# Power_section.net
KiCad netlist of a schematic drawn in Altium Designer
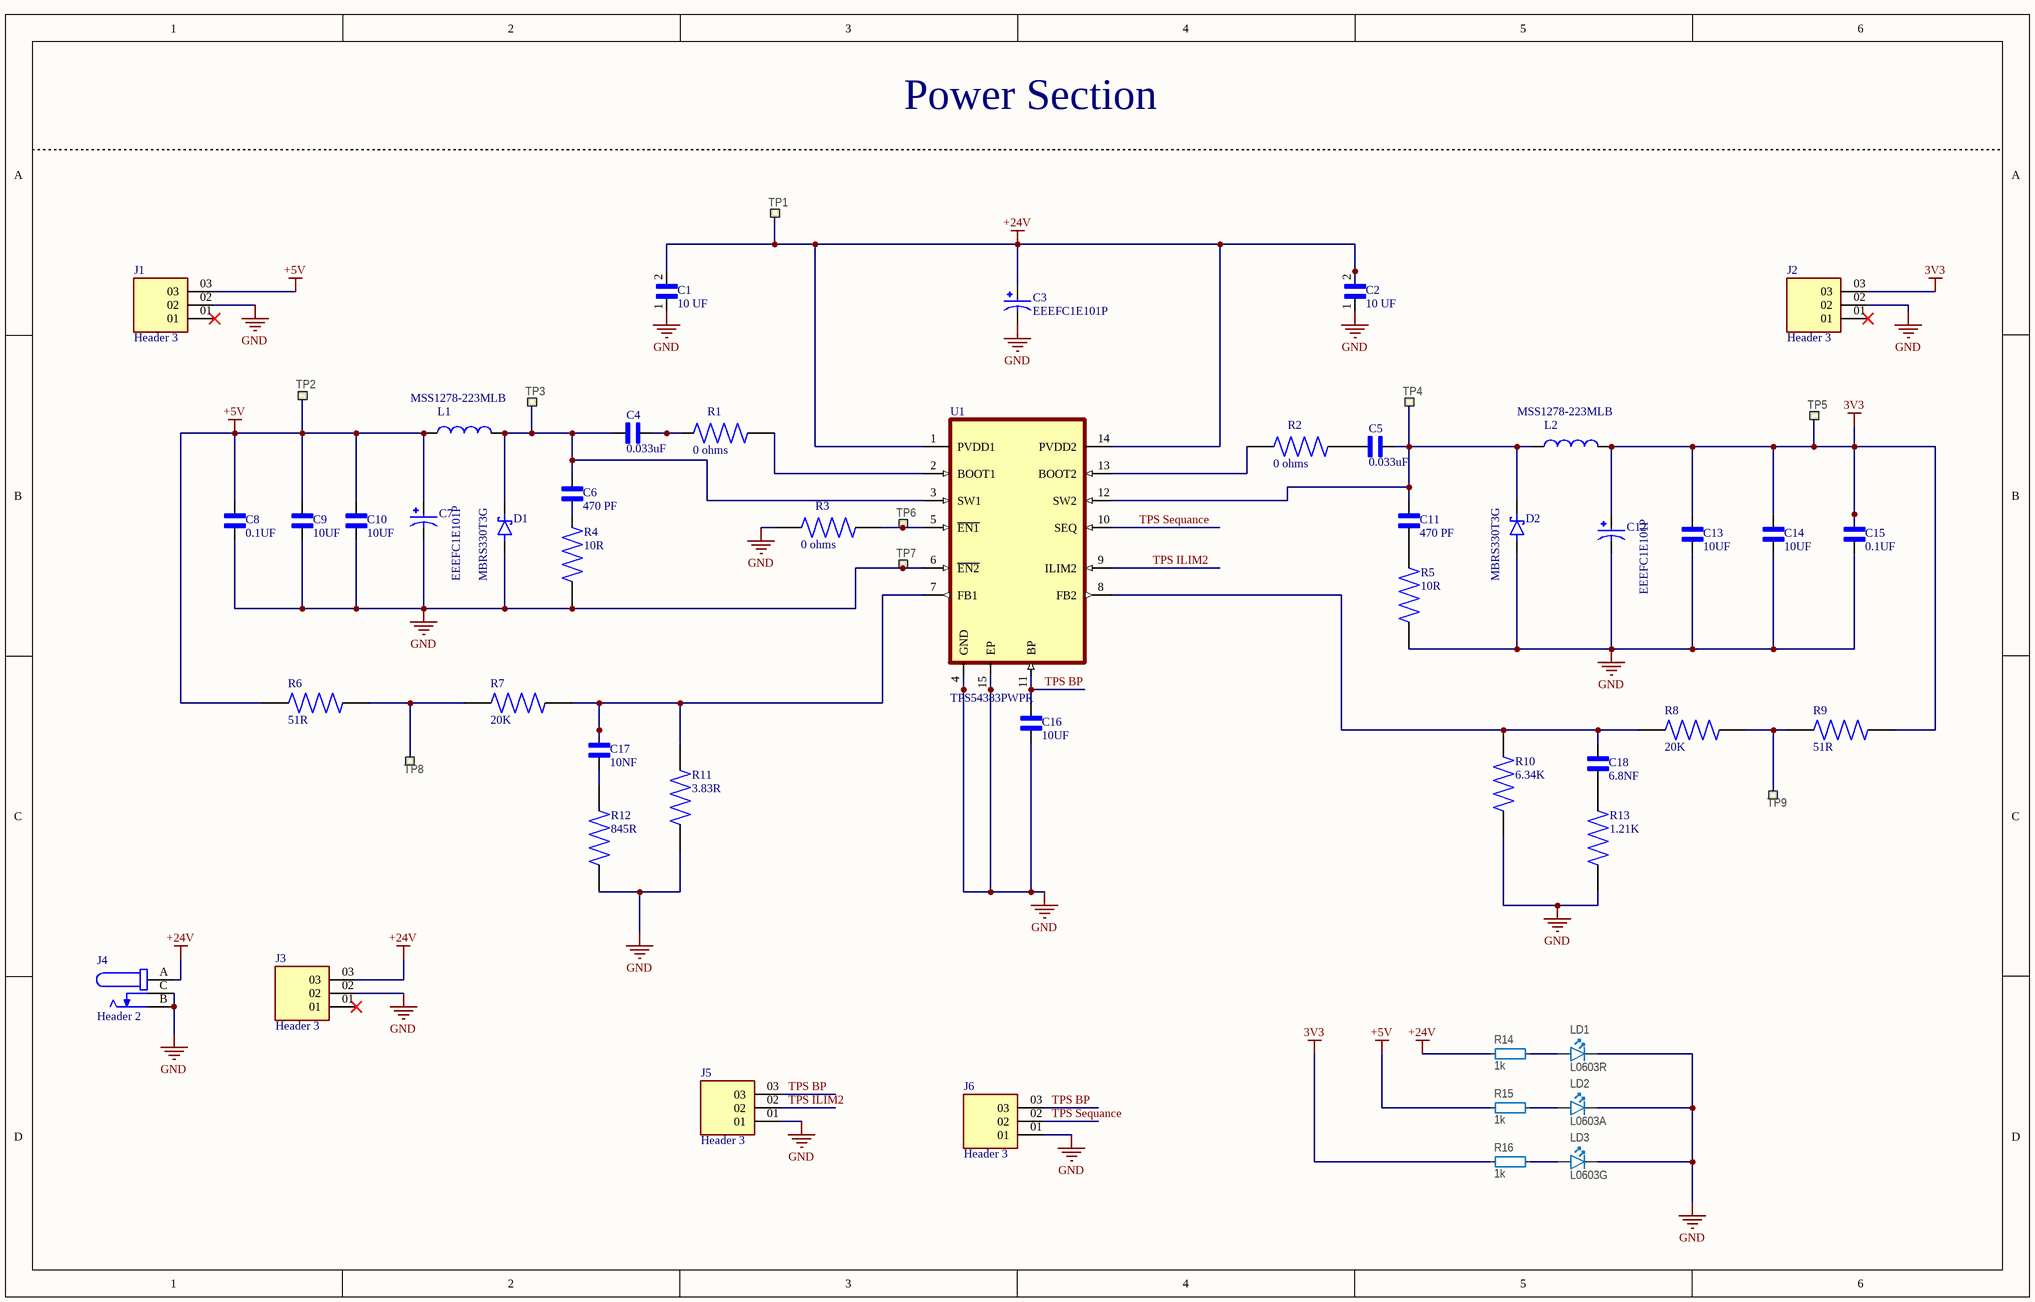
[diagram p0: Power section.SchDoc]

(export (version "E")
  (design (tool "Eeschema 10.0.6"))
  (components
    (comp (ref "C1")
      (value "10 UF")
      (footprint "CAPC3216X180N")
      (description "10礔 卤20% 25V Ceramic Capacitor 1206 (3216 Metric)")
      (fields (field (name "MF") "TDK") (field (name "DIGI-KEY_PART_NUMBER") "445-7708-2-ND"))
      (libsource (lib "C3216X5R1E106M160AB") (part "C3216X5R1E106M160AB"))
    )
    (comp (ref "C2")
      (value "10 UF")
      (footprint "CAPC3216X180N")
      (description "10礔 卤20% 25V Ceramic Capacitor 1206 (3216 Metric)")
      (fields (field (name "MF") "TDK") (field (name "DIGI-KEY_PART_NUMBER") "445-7708-2-ND"))
      (libsource (lib "C3216X5R1E106M160AB") (part "C3216X5R1E106M160AB"))
    )
    (comp (ref "C3")
      (value "EEEFC1E101P")
      (footprint "CAP_EEEFC1E101P")
      (fields (field (name "MF") "Panasonic") (field (name "MP") "EEE-FC1E101P"))
      (libsource (lib "EEEFC1E101P") (part "EEEFC1E101P"))
    )
    (comp (ref "C4")
      (value "0.033uF")
      (footprint "CAPC1608X90")
      (description "Capacitor, ceramic, 25 V, X7R, 20%, .033 μF, 0603")
      (fields (field (name "MF") "KEMET") (field (name "MP") "C0603C104J3RACTU"))
      (libsource (lib "") (part "C0603C104J3RACTU_1"))
    )
    (comp (ref "C5")
      (value "0.033uF")
      (footprint "CAPC1608X90")
      (description "Capacitor, ceramic, 25 V, X7R, 20%, .033 μF, 0603")
      (fields (field (name "MF") "KEMET") (field (name "MP") "C0603C104J3RACTU"))
      (libsource (lib "") (part "C0603C104J3RACTU_1"))
    )
    (comp (ref "C6")
      (value "470 PF")
      (footprint "CAPC1608X90")
      (description "Capacitor, ceramic, 25 V, X7R, 20%, 470 pF, 0603")
      (fields (field (name "MF") "KEMET") (field (name "MP") "C0603C104J3RACTU"))
      (libsource (lib "Accelo Integrated_Library") (part "C0603C104J3RACTU"))
    )
    (comp (ref "C7")
      (value "EEEFC1E101P")
      (footprint "CAP_EEEFC1E101P")
      (fields (field (name "MF") "Panasonic") (field (name "MP") "EEE-FC1E101P"))
      (libsource (lib "EEEFC1E101P") (part "EEEFC1E101P"))
    )
    (comp (ref "C8")
      (value "0.1UF")
      (footprint "CAPC1608X90")
      (description "Capacitor, ceramic, 10 V, X7R, 20%, 0.1 μF, 0603")
      (fields (field (name "MF") "KEMET") (field (name "MP") "C0603C104J3RACTU"))
      (libsource (lib "Accelo Integrated_Library") (part "C0603C104J3RACTU"))
    )
    (comp (ref "C9")
      (value "10UF")
      (footprint "CAPC2012X140N")
      (description "Capacitor, ceramic, 6.3 V, X5R, 20%, 10 μF, 0805")
      (fields (field (name "MF") "AVX") (field (name "MP") "0805ZD474MAT2A"))
      (libsource (lib "0805ZD474MAT2A") (part "0805ZD474MAT2A"))
    )
    (comp (ref "C10")
      (value "10UF")
      (footprint "CAPC2012X140N")
      (description "Capacitor, ceramic, 6.3 V, X5R, 20%, 10 μF, 0805")
      (fields (field (name "MF") "AVX") (field (name "MP") "0805ZD474MAT2A"))
      (libsource (lib "0805ZD474MAT2A") (part "0805ZD474MAT2A"))
    )
    (comp (ref "C11")
      (value "470 PF")
      (footprint "CAPC1608X90")
      (description "Capacitor, ceramic, 25 V, X7R, 20%, 470 pF, 0603")
      (fields (field (name "MF") "KEMET") (field (name "MP") "C0603C104J3RACTU"))
      (libsource (lib "Accelo Integrated_Library") (part "C0603C104J3RACTU"))
    )
    (comp (ref "C12")
      (value "EEEFC1E101P")
      (footprint "CAP_EEEFC1E101P")
      (fields (field (name "MF") "Panasonic") (field (name "MP") "EEE-FC1E101P"))
      (libsource (lib "EEEFC1E101P") (part "EEEFC1E101P"))
    )
    (comp (ref "C13")
      (value "10UF")
      (footprint "CAPC2012X140N")
      (description "Capacitor, ceramic, 6.3 V, X5R, 20%, 10 μF, 0805")
      (fields (field (name "MF") "AVX") (field (name "MP") "0805ZD474MAT2A"))
      (libsource (lib "0805ZD474MAT2A") (part "0805ZD474MAT2A"))
    )
    (comp (ref "C14")
      (value "10UF")
      (footprint "CAPC2012X140N")
      (description "Capacitor, ceramic, 6.3 V, X5R, 20%, 10 μF, 0805")
      (fields (field (name "MF") "AVX") (field (name "MP") "0805ZD474MAT2A"))
      (libsource (lib "0805ZD474MAT2A") (part "0805ZD474MAT2A"))
    )
    (comp (ref "C15")
      (value "0.1UF")
      (footprint "CAPC1608X90")
      (description "Capacitor, ceramic, 10 V, X7R, 20%, 0.1 μF, 0603")
      (fields (field (name "MF") "KEMET") (field (name "MP") "C0603C104J3RACTU"))
      (libsource (lib "Accelo Integrated_Library") (part "C0603C104J3RACTU"))
    )
    (comp (ref "C16")
      (value "10UF")
      (footprint "CAPC2012X140N")
      (description "0.47 ÂµF Â±20% 10V Ceramic Capacitor X5R 0805 (2012 Metric)")
      (fields (field (name "MF") "AVX") (field (name "MP") "0805ZD474MAT2A"))
      (libsource (lib "0805ZD474MAT2A") (part "0805ZD474MAT2A"))
    )
    (comp (ref "C17")
      (value "10NF")
      (footprint "CAPC1608X90")
      (fields (field (name "MF") "KEMET") (field (name "MP") "C0603C104J3RACTU"))
      (libsource (lib "Accelo Integrated_Library") (part "C0603C104J3RACTU"))
    )
    (comp (ref "C18")
      (value "6.8NF")
      (footprint "CAPC1608X90")
      (fields (field (name "MF") "KEMET") (field (name "MP") "C0603C104J3RACTU"))
      (libsource (lib "Accelo Integrated_Library") (part "C0603C104J3RACTU"))
    )
    (comp (ref "D1")
      (value "MBRS330T3G")
      (footprint "DIOM7959X261N")
      (description "Diode Schottky 30 V 3A Surface Mount SMC")
      (fields (field (name "MF") "ON Semiconductor"))
      (libsource (lib "MBRS330T3G") (part "MBRS330T3G"))
    )
    (comp (ref "D2")
      (value "MBRS330T3G")
      (footprint "DIOM7959X261N")
      (description "Diode Schottky 30 V 3A Surface Mount SMC")
      (fields (field (name "MF") "ON Semiconductor"))
      (libsource (lib "MBRS330T3G") (part "MBRS330T3G"))
    )
    (comp (ref "J1")
      (value "Header 3")
      (footprint "SAMTEC_HMTSW-103-XX-X-S-XXX")
      (description "Connector Unshrouded Header 3 Position 2.54mm Solder Straight Through Hole")
      (fields (field (name "MF") "Samtec") (field (name "MP") "HMTSW-103-10-T-S-330"))
      (libsource (lib "Accelo Integrated_Library") (part "HMTSW-103-XX-X-S-XXX"))
    )
    (comp (ref "J2")
      (value "Header 3")
      (footprint "SAMTEC_HMTSW-103-XX-X-S-XXX")
      (description "Connector Unshrouded Header 3 Position 2.54mm Solder Straight Through Hole")
      (fields (field (name "MF") "Samtec") (field (name "MP") "HMTSW-103-10-T-S-330"))
      (libsource (lib "Accelo Integrated_Library") (part "HMTSW-103-XX-X-S-XXX"))
    )
    (comp (ref "J3")
      (value "Header 3")
      (footprint "SAMTEC_HMTSW-103-XX-X-S-XXX")
      (description "Connector Unshrouded Header 3 Position 2.54mm Solder Straight Through Hole")
      (fields (field (name "MF") "Samtec") (field (name "MP") "HMTSW-103-10-T-S-330"))
      (libsource (lib "Accelo Integrated_Library") (part "HMTSW-103-XX-X-S-XXX"))
    )
    (comp (ref "J4")
      (value "Header 2")
      (footprint "TENSILITY_54-00129")
      (description "Connector, dc jack 5.5x2.1 mm, PCB mount, 90 degrees, silver plated, thru hole")
      (fields (field (name "MF") "Tensility International Corp") (field (name "MP") "54-00129"))
      (libsource (lib "54-00129") (part "54-00129"))
    )
    (comp (ref "J5")
      (value "Header 3")
      (footprint "SAMTEC_HMTSW-103-XX-X-S-XXX")
      (description "Connector Unshrouded Header 3 Position 2.54mm Solder Straight Through Hole")
      (fields (field (name "MF") "Samtec") (field (name "MP") "HMTSW-103-10-T-S-330"))
      (libsource (lib "Accelo Integrated_Library") (part "HMTSW-103-XX-X-S-XXX"))
    )
    (comp (ref "J6")
      (value "Header 3")
      (footprint "SAMTEC_HMTSW-103-XX-X-S-XXX")
      (description "Connector Unshrouded Header 3 Position 2.54mm Solder Straight Through Hole")
      (fields (field (name "MF") "Samtec") (field (name "MP") "HMTSW-103-10-T-S-330"))
      (libsource (lib "Accelo Integrated_Library") (part "HMTSW-103-XX-X-S-XXX"))
    )
    (comp (ref "L1")
      (value "MSS1278-223MLB")
      (footprint "IND_MSS1278-223MLB")
      (description "Fixed Inductors 22uH Shld 20% 4A 39.5mOhms AECQ2")
      (fields (field (name "MF") "Coilcraft"))
      (libsource (lib "MSS1278-223MLB") (part "MSS1278-223MLB"))
    )
    (comp (ref "L2")
      (value "MSS1278-223MLB")
      (footprint "IND_MSS1278-223MLB")
      (description "Fixed Inductors 22uH Shld 20% 4A 39.5mOhms AECQ2")
      (fields (field (name "MF") "Coilcraft"))
      (libsource (lib "MSS1278-223MLB") (part "MSS1278-223MLB"))
    )
    (comp (ref "LD1")
      (value "L0603R")
      (footprint "LED_0603_R")
      (description "LED, Red, 0603, Vf=2V, - 40 to +100°C")
      (fields
        (field (name "PART NUMBER") "ASMT-RR45-AQ902")
        (field (name "MANUFACTURER") "Avago")
        (field (name "AUTHOR") "rsk")
      )
      (libsource (lib "pca10152") (part "ASMT-RR45-AQ902"))
    )
    (comp (ref "LD2")
      (value "L0603A")
      (footprint "LED_0603_Y")
      (description "LED, Amber, 0603,  Vf=2V, - 40 to +100°C")
      (fields
        (field (name "PART NUMBER") "ASMT-RA45-AP932")
        (field (name "MANUFACTURER") "Avago")
        (field (name "AUTHOR") "rsk")
      )
      (libsource (lib "pca10152") (part "ASMT-RA45-AP932"))
    )
    (comp (ref "LD3")
      (value "L0603G")
      (footprint "LED_0603_G")
      (description "LED, Yellow Green, 0603, Vf=2V, - 40 to +100°C")
      (fields
        (field (name "PART NUMBER") "ASMT-RF45-AN002")
        (field (name "MANUFACTURER") "Avago")
        (field (name "AUTHOR") "rsk")
      )
      (libsource (lib "pca10152") (part "ASMT-RF45-AN002"))
    )
    (comp (ref "R1")
      (value "0 ohms")
      (footprint "RESC1608X55N")
      (description "Resistor, chip, 1/16 W, 5%, 0 Ω, 0603")
      (fields (field (name "MF") "Yageo") (field (name "MP") "RC0603JR-0751RL"))
      (libsource (lib "RC0603JR-0751RL") (part "RC0603JR-0751RL"))
    )
    (comp (ref "R2")
      (value "0 ohms")
      (footprint "RESC1608X55N")
      (description "Resistor, chip, 1/16 W, 5%, 0 Ω, 0603")
      (fields (field (name "MF") "Yageo") (field (name "MP") "RC0603JR-0751RL"))
      (libsource (lib "RC0603JR-0751RL") (part "RC0603JR-0751RL"))
    )
    (comp (ref "R3")
      (value "0 ohms")
      (footprint "RESC1608X55N")
      (description "Resistor, chip, 1/16 W, 5%, 0 Ω, 0603")
      (fields (field (name "MF") "Yageo") (field (name "MP") "RC0603JR-0751RL"))
      (libsource (lib "RC0603JR-0751RL") (part "RC0603JR-0751RL"))
    )
    (comp (ref "R4")
      (value "10R")
      (footprint "RESC1608X55N")
      (description "Resistor, chip, 1/16 W, 5%, 10 Ω, 0603")
      (fields (field (name "MF") "Yageo") (field (name "MP") "RC0603JR-0751RL"))
      (libsource (lib "RC0603JR-0751RL") (part "RC0603JR-0751RL"))
    )
    (comp (ref "R5")
      (value "10R")
      (footprint "RESC1608X55N")
      (description "Resistor, chip, 1/16 W, 5%, 10 Ω, 0603")
      (fields (field (name "MF") "Yageo") (field (name "MP") "RC0603JR-0751RL"))
      (libsource (lib "RC0603JR-0751RL") (part "RC0603JR-0751RL"))
    )
    (comp (ref "R6")
      (value "51R")
      (footprint "RESC1608X55N")
      (description "51 Ohms Â±5% 0.1W, 1/10W Chip Resistor 0603 (1608 Metric) Moisture Resistant Thick Film")
      (fields (field (name "MF") "Yageo") (field (name "MP") "RC0603JR-0751RL"))
      (libsource (lib "RC0603JR-0751RL") (part "RC0603JR-0751RL"))
    )
    (comp (ref "R7")
      (value "20K")
      (footprint "RESC1608X55N")
      (description "51 Ohms Â±5% 0.1W, 1/10W Chip Resistor 0603 (1608 Metric) Moisture Resistant Thick Film")
      (fields (field (name "MF") "Yageo") (field (name "MP") "RC0603JR-0751RL"))
      (libsource (lib "RC0603JR-0751RL") (part "RC0603JR-0751RL"))
    )
    (comp (ref "R8")
      (value "20K")
      (footprint "RESC1608X55N")
      (description "51 Ohms Â±5% 0.1W, 1/10W Chip Resistor 0603 (1608 Metric) Moisture Resistant Thick Film")
      (fields (field (name "MF") "Yageo") (field (name "MP") "RC0603JR-0751RL"))
      (libsource (lib "RC0603JR-0751RL") (part "RC0603JR-0751RL"))
    )
    (comp (ref "R9")
      (value "51R")
      (footprint "RESC1608X55N")
      (description "51 Ohms Â±5% 0.1W, 1/10W Chip Resistor 0603 (1608 Metric) Moisture Resistant Thick Film")
      (fields (field (name "MF") "Yageo") (field (name "MP") "RC0603JR-0751RL"))
      (libsource (lib "RC0603JR-0751RL") (part "RC0603JR-0751RL"))
    )
    (comp (ref "R10")
      (value "6.34K")
      (footprint "RESC1608X55N")
      (description "51 Ohms Â±5% 0.1W, 1/10W Chip Resistor 0603 (1608 Metric) Moisture Resistant Thick Film")
      (fields (field (name "MF") "Yageo") (field (name "MP") "RC0603JR-0751RL"))
      (libsource (lib "RC0603JR-0751RL") (part "RC0603JR-0751RL"))
    )
    (comp (ref "R11")
      (value "3.83R")
      (footprint "RESC1608X55N")
      (description "51 Ohms Â±5% 0.1W, 1/10W Chip Resistor 0603 (1608 Metric) Moisture Resistant Thick Film")
      (fields (field (name "MF") "Yageo") (field (name "MP") "RC0603JR-0751RL"))
      (libsource (lib "RC0603JR-0751RL") (part "RC0603JR-0751RL"))
    )
    (comp (ref "R12")
      (value "845R")
      (footprint "RESC1608X55N")
      (description "51 Ohms Â±5% 0.1W, 1/10W Chip Resistor 0603 (1608 Metric) Moisture Resistant Thick Film")
      (fields (field (name "MF") "Yageo") (field (name "MP") "RC0603JR-0751RL"))
      (libsource (lib "RC0603JR-0751RL") (part "RC0603JR-0751RL"))
    )
    (comp (ref "R13")
      (value "1.21K")
      (footprint "RESC1608X55N")
      (description "51 Ohms Â±5% 0.1W, 1/10W Chip Resistor 0603 (1608 Metric) Moisture Resistant Thick Film")
      (fields (field (name "MF") "Yageo") (field (name "MP") "RC0603JR-0751RL"))
      (libsource (lib "RC0603JR-0751RL") (part "RC0603JR-0751RL"))
    )
    (comp (ref "R14")
      (value "1k")
      (footprint "RESC0603X03L_C")
      (description "Resistor, ±1%, 0.05W")
      (fields
        (field (name "PART NUMBER") "R0201-1k0")
        (field (name "MANUFACTURER") "N.A.")
        (field (name "AUTHOR") "rsk")
      )
      (libsource (lib "pca10152") (part "R0201-1k0"))
    )
    (comp (ref "R15")
      (value "1k")
      (footprint "RESC0603X03L_C")
      (description "Resistor, ±1%, 0.05W")
      (fields
        (field (name "PART NUMBER") "R0201-1k0")
        (field (name "MANUFACTURER") "N.A.")
        (field (name "AUTHOR") "rsk")
      )
      (libsource (lib "pca10152") (part "R0201-1k0"))
    )
    (comp (ref "R16")
      (value "1k")
      (footprint "RESC0603X03L_C")
      (description "Resistor, ±1%, 0.05W")
      (fields
        (field (name "PART NUMBER") "R0201-1k0")
        (field (name "MANUFACTURER") "N.A.")
        (field (name "AUTHOR") "rsk")
      )
      (libsource (lib "pca10152") (part "R0201-1k0"))
    )
    (comp (ref "TP1")
      (value "Ø0.7mm,SMD")
      (footprint "TP_SMD_D0.7mm")
      (description "0.7mm circular SMD testpad")
      (fields
        (field (name "PART NUMBER") "TP_SMD_Ø0.7MM")
        (field (name "MANUFACTURER") "Nordic Semiconductor")
        (field (name "AUTHOR") "rsk")
      )
      (libsource (lib "") (part "TP_SMD_Ø0.7MM_1"))
    )
    (comp (ref "TP2")
      (value "Ø0.7mm,SMD")
      (footprint "TP_SMD_D0.7mm")
      (description "0.7mm circular SMD testpad")
      (fields
        (field (name "PART NUMBER") "TP_SMD_Ø0.7MM")
        (field (name "MANUFACTURER") "Nordic Semiconductor")
        (field (name "AUTHOR") "rsk")
      )
      (libsource (lib "") (part "TP_SMD_Ø0.7MM_1"))
    )
    (comp (ref "TP3")
      (value "Ø0.7mm,SMD")
      (footprint "TP_SMD_D0.7mm")
      (description "0.7mm circular SMD testpad")
      (fields
        (field (name "PART NUMBER") "TP_SMD_Ø0.7MM")
        (field (name "MANUFACTURER") "Nordic Semiconductor")
        (field (name "AUTHOR") "rsk")
      )
      (libsource (lib "") (part "TP_SMD_Ø0.7MM_1"))
    )
    (comp (ref "TP4")
      (value "Ø0.7mm,SMD")
      (footprint "TP_SMD_D0.7mm")
      (description "0.7mm circular SMD testpad")
      (fields
        (field (name "PART NUMBER") "TP_SMD_Ø0.7MM")
        (field (name "MANUFACTURER") "Nordic Semiconductor")
        (field (name "AUTHOR") "rsk")
      )
      (libsource (lib "") (part "TP_SMD_Ø0.7MM_1"))
    )
    (comp (ref "TP5")
      (value "Ø0.7mm,SMD")
      (footprint "TP_SMD_D0.7mm")
      (description "0.7mm circular SMD testpad")
      (fields
        (field (name "PART NUMBER") "TP_SMD_Ø0.7MM")
        (field (name "MANUFACTURER") "Nordic Semiconductor")
        (field (name "AUTHOR") "rsk")
      )
      (libsource (lib "") (part "TP_SMD_Ø0.7MM_1"))
    )
    (comp (ref "TP6")
      (value "Ø0.7mm,SMD")
      (footprint "TP_SMD_D0.7mm")
      (description "0.7mm circular SMD testpad")
      (fields
        (field (name "PART NUMBER") "TP_SMD_Ø0.7MM")
        (field (name "MANUFACTURER") "Nordic Semiconductor")
        (field (name "AUTHOR") "rsk")
      )
      (libsource (lib "") (part "TP_SMD_Ø0.7MM_1"))
    )
    (comp (ref "TP7")
      (value "Ø0.7mm,SMD")
      (footprint "TP_SMD_D0.7mm")
      (description "0.7mm circular SMD testpad")
      (fields
        (field (name "PART NUMBER") "TP_SMD_Ø0.7MM")
        (field (name "MANUFACTURER") "Nordic Semiconductor")
        (field (name "AUTHOR") "rsk")
      )
      (libsource (lib "") (part "TP_SMD_Ø0.7MM_1"))
    )
    (comp (ref "TP8")
      (value "Ø0.7mm,SMD")
      (footprint "TP_SMD_D0.7mm")
      (description "0.7mm circular SMD testpad")
      (fields
        (field (name "PART NUMBER") "TP_SMD_Ø0.7MM")
        (field (name "MANUFACTURER") "Nordic Semiconductor")
        (field (name "AUTHOR") "rsk")
      )
      (libsource (lib "pca10152") (part "TP_SMD_Ø0.7MM"))
    )
    (comp (ref "TP9")
      (value "Ø0.7mm,SMD")
      (footprint "TP_SMD_D0.7mm")
      (description "0.7mm circular SMD testpad")
      (fields
        (field (name "PART NUMBER") "TP_SMD_Ø0.7MM")
        (field (name "MANUFACTURER") "Nordic Semiconductor")
        (field (name "AUTHOR") "rsk")
      )
      (libsource (lib "pca10152") (part "TP_SMD_Ø0.7MM"))
    )
    (comp (ref "U1")
      (value "TPS54383PWPR")
      (footprint "IC_TPS27S100BPWPR")
      (fields (field (name "MF") "{'manufacturer': u'Texas Instruments'}"))
      (libsource (lib "TP") (part "TPS54383PWPR"))
    )
  )
  (nets
    (net (code "1") (name "+5V") (class "Default")
      (node (ref "C10") (pin "1") (pinfunction "1_1") (pintype "passive"))
      (node (ref "C7") (pin "1") (pinfunction "1_1") (pintype "passive"))
      (node (ref "C8") (pin "1") (pinfunction "1_1") (pintype "passive"))
      (node (ref "C9") (pin "1") (pinfunction "1_1") (pintype "passive"))
      (node (ref "J1") (pin "03") (pinfunction "03_03") (pintype "passive"))
      (node (ref "L1") (pin "1") (pinfunction "1_1") (pintype "passive"))
      (node (ref "R15") (pin "1") (pinfunction "1_1") (pintype "passive"))
      (node (ref "R6") (pin "2") (pinfunction "2_2") (pintype "passive"))
      (node (ref "TP2") (pin "1") (pinfunction "1_1") (pintype "passive"))
    )
    (net (code "2") (name "+24V") (class "Default")
      (node (ref "C1") (pin "2") (pinfunction "2_2") (pintype "passive"))
      (node (ref "C2") (pin "2") (pinfunction "2_2") (pintype "passive"))
      (node (ref "C3") (pin "1") (pinfunction "1_1") (pintype "passive"))
      (node (ref "J3") (pin "03") (pinfunction "03_03") (pintype "passive"))
      (node (ref "J4") (pin "A") (pinfunction "A_A") (pintype "passive"))
      (node (ref "R14") (pin "1") (pinfunction "1_1") (pintype "passive"))
      (node (ref "TP1") (pin "1") (pinfunction "1_1") (pintype "passive"))
      (node (ref "U1") (pin "1") (pinfunction "PVDD1_1") (pintype "power_in"))
      (node (ref "U1") (pin "14") (pinfunction "PVDD2_14") (pintype "power_in"))
    )
    (net (code "3") (name "/TPS BP") (class "Default")
      (node (ref "C16") (pin "1") (pinfunction "1_1") (pintype "passive"))
      (node (ref "J5") (pin "03") (pinfunction "03_03") (pintype "passive"))
      (node (ref "J6") (pin "03") (pinfunction "03_03") (pintype "passive"))
      (node (ref "U1") (pin "11") (pinfunction "BP_11") (pintype "input"))
    )
    (net (code "4") (name "/TPS ILIM2") (class "Default")
      (node (ref "J5") (pin "02") (pinfunction "02_02") (pintype "passive"))
      (node (ref "U1") (pin "9") (pinfunction "ILIM2_9") (pintype "input"))
    )
    (net (code "5") (name "/TPS Sequance") (class "Default")
      (node (ref "J6") (pin "02") (pinfunction "02_02") (pintype "passive"))
      (node (ref "U1") (pin "10") (pinfunction "SEQ_10") (pintype "input"))
    )
    (net (code "6") (name "3V3") (class "Default")
      (node (ref "C12") (pin "1") (pinfunction "1_1") (pintype "passive"))
      (node (ref "C13") (pin "1") (pinfunction "1_1") (pintype "passive"))
      (node (ref "C14") (pin "1") (pinfunction "1_1") (pintype "passive"))
      (node (ref "C15") (pin "1") (pinfunction "1_1") (pintype "passive"))
      (node (ref "J2") (pin "03") (pinfunction "03_03") (pintype "passive"))
      (node (ref "L2") (pin "2") (pinfunction "2_2") (pintype "passive"))
      (node (ref "R16") (pin "1") (pinfunction "1_1") (pintype "passive"))
      (node (ref "R9") (pin "1") (pinfunction "1_1") (pintype "passive"))
      (node (ref "TP5") (pin "1") (pinfunction "1_1") (pintype "passive"))
    )
    (net (code "7") (name "GND") (class "Default")
      (node (ref "C1") (pin "1") (pinfunction "1_1") (pintype "passive"))
      (node (ref "C10") (pin "2") (pinfunction "2_2") (pintype "passive"))
      (node (ref "C12") (pin "2") (pinfunction "2_2") (pintype "passive"))
      (node (ref "C13") (pin "2") (pinfunction "2_2") (pintype "passive"))
      (node (ref "C14") (pin "2") (pinfunction "2_2") (pintype "passive"))
      (node (ref "C15") (pin "2") (pinfunction "2_2") (pintype "passive"))
      (node (ref "C16") (pin "2") (pinfunction "2_2") (pintype "passive"))
      (node (ref "C2") (pin "1") (pinfunction "1_1") (pintype "passive"))
      (node (ref "C3") (pin "2") (pinfunction "2_2") (pintype "passive"))
      (node (ref "C7") (pin "2") (pinfunction "2_2") (pintype "passive"))
      (node (ref "C8") (pin "2") (pinfunction "2_2") (pintype "passive"))
      (node (ref "C9") (pin "2") (pinfunction "2_2") (pintype "passive"))
      (node (ref "D1") (pin "A") (pinfunction "A_A") (pintype "passive"))
      (node (ref "D2") (pin "A") (pinfunction "A_A") (pintype "passive"))
      (node (ref "J1") (pin "02") (pinfunction "02_02") (pintype "passive"))
      (node (ref "J2") (pin "02") (pinfunction "02_02") (pintype "passive"))
      (node (ref "J3") (pin "02") (pinfunction "02_02") (pintype "passive"))
      (node (ref "J4") (pin "B") (pinfunction "B_B") (pintype "passive"))
      (node (ref "J4") (pin "C") (pinfunction "C_C") (pintype "passive"))
      (node (ref "J5") (pin "01") (pinfunction "01_01") (pintype "passive"))
      (node (ref "J6") (pin "01") (pinfunction "01_01") (pintype "passive"))
      (node (ref "LD1") (pin "1") (pinfunction "C_1") (pintype "passive"))
      (node (ref "LD2") (pin "1") (pinfunction "C_1") (pintype "passive"))
      (node (ref "LD3") (pin "1") (pinfunction "C_1") (pintype "passive"))
      (node (ref "R10") (pin "1") (pinfunction "1_1") (pintype "passive"))
      (node (ref "R11") (pin "1") (pinfunction "1_1") (pintype "passive"))
      (node (ref "R12") (pin "1") (pinfunction "1_1") (pintype "passive"))
      (node (ref "R13") (pin "1") (pinfunction "1_1") (pintype "passive"))
      (node (ref "R3") (pin "1") (pinfunction "1_1") (pintype "passive"))
      (node (ref "R4") (pin "1") (pinfunction "1_1") (pintype "passive"))
      (node (ref "R5") (pin "1") (pinfunction "1_1") (pintype "passive"))
      (node (ref "TP7") (pin "1") (pinfunction "1_1") (pintype "passive"))
      (node (ref "U1") (pin "15") (pinfunction "EP_15") (pintype "power_in"))
      (node (ref "U1") (pin "4") (pinfunction "GND_4") (pintype "power_in"))
      (node (ref "U1") (pin "6") (pinfunction "~{EN2}_6") (pintype "input"))
    )
    (net (code "8") (name "Net-(C4-Pad1)") (class "Default")
      (node (ref "C4") (pin "1") (pinfunction "1_1") (pintype "passive"))
      (node (ref "R1") (pin "1") (pinfunction "1_1") (pintype "passive"))
    )
    (net (code "9") (name "Net-(C5-Pad2)") (class "Default")
      (node (ref "C5") (pin "2") (pinfunction "2_2") (pintype "passive"))
      (node (ref "R2") (pin "2") (pinfunction "2_2") (pintype "passive"))
    )
    (net (code "10") (name "Net-(C6-Pad2)") (class "Default")
      (node (ref "C6") (pin "2") (pinfunction "2_2") (pintype "passive"))
      (node (ref "R4") (pin "2") (pinfunction "2_2") (pintype "passive"))
    )
    (net (code "11") (name "Net-(C11-Pad2)") (class "Default")
      (node (ref "C11") (pin "2") (pinfunction "2_2") (pintype "passive"))
      (node (ref "R5") (pin "2") (pinfunction "2_2") (pintype "passive"))
    )
    (net (code "12") (name "Net-(C17-Pad2)") (class "Default")
      (node (ref "C17") (pin "2") (pinfunction "2_2") (pintype "passive"))
      (node (ref "R12") (pin "2") (pinfunction "2_2") (pintype "passive"))
    )
    (net (code "13") (name "Net-(C18-Pad2)") (class "Default")
      (node (ref "C18") (pin "2") (pinfunction "2_2") (pintype "passive"))
      (node (ref "R13") (pin "2") (pinfunction "2_2") (pintype "passive"))
    )
    (net (code "14") (name "Net-(D1-K)") (class "Default")
      (node (ref "C4") (pin "2") (pinfunction "2_2") (pintype "passive"))
      (node (ref "C6") (pin "1") (pinfunction "1_1") (pintype "passive"))
      (node (ref "D1") (pin "C") (pinfunction "K_C") (pintype "passive"))
      (node (ref "L1") (pin "2") (pinfunction "2_2") (pintype "passive"))
      (node (ref "TP3") (pin "1") (pinfunction "1_1") (pintype "passive"))
      (node (ref "U1") (pin "3") (pinfunction "SW1_3") (pintype "input"))
    )
    (net (code "15") (name "Net-(D2-K)") (class "Default")
      (node (ref "C11") (pin "1") (pinfunction "1_1") (pintype "passive"))
      (node (ref "C5") (pin "1") (pinfunction "1_1") (pintype "passive"))
      (node (ref "D2") (pin "C") (pinfunction "K_C") (pintype "passive"))
      (node (ref "L2") (pin "1") (pinfunction "1_1") (pintype "passive"))
      (node (ref "TP4") (pin "1") (pinfunction "1_1") (pintype "passive"))
      (node (ref "U1") (pin "12") (pinfunction "SW2_12") (pintype "input"))
    )
    (net (code "16") (name "Net-(LD1-A)") (class "Default")
      (node (ref "LD1") (pin "2") (pinfunction "A_2") (pintype "passive"))
      (node (ref "R14") (pin "2") (pinfunction "2_2") (pintype "passive"))
    )
    (net (code "17") (name "Net-(LD2-A)") (class "Default")
      (node (ref "LD2") (pin "2") (pinfunction "A_2") (pintype "passive"))
      (node (ref "R15") (pin "2") (pinfunction "2_2") (pintype "passive"))
    )
    (net (code "18") (name "Net-(LD3-A)") (class "Default")
      (node (ref "LD3") (pin "2") (pinfunction "A_2") (pintype "passive"))
      (node (ref "R16") (pin "2") (pinfunction "2_2") (pintype "passive"))
    )
    (net (code "19") (name "Net-(R6-Pad1)") (class "Default")
      (node (ref "R6") (pin "1") (pinfunction "1_1") (pintype "passive"))
      (node (ref "R7") (pin "2") (pinfunction "2_2") (pintype "passive"))
      (node (ref "TP8") (pin "1") (pinfunction "1_1") (pintype "passive"))
    )
    (net (code "20") (name "Net-(R8-Pad1)") (class "Default")
      (node (ref "R8") (pin "1") (pinfunction "1_1") (pintype "passive"))
      (node (ref "R9") (pin "2") (pinfunction "2_2") (pintype "passive"))
      (node (ref "TP9") (pin "1") (pinfunction "1_1") (pintype "passive"))
    )
    (net (code "21") (name "Net-(U1-BOOT1)") (class "Default")
      (node (ref "R1") (pin "2") (pinfunction "2_2") (pintype "passive"))
      (node (ref "U1") (pin "2") (pinfunction "BOOT1_2") (pintype "input"))
    )
    (net (code "22") (name "Net-(U1-BOOT2)") (class "Default")
      (node (ref "R2") (pin "1") (pinfunction "1_1") (pintype "passive"))
      (node (ref "U1") (pin "13") (pinfunction "BOOT2_13") (pintype "input"))
    )
    (net (code "23") (name "Net-(U1-FB1)") (class "Default")
      (node (ref "C17") (pin "1") (pinfunction "1_1") (pintype "passive"))
      (node (ref "R11") (pin "2") (pinfunction "2_2") (pintype "passive"))
      (node (ref "R7") (pin "1") (pinfunction "1_1") (pintype "passive"))
      (node (ref "U1") (pin "7") (pinfunction "FB1_7") (pintype "output"))
    )
    (net (code "24") (name "Net-(U1-FB2)") (class "Default")
      (node (ref "C18") (pin "1") (pinfunction "1_1") (pintype "passive"))
      (node (ref "R10") (pin "2") (pinfunction "2_2") (pintype "passive"))
      (node (ref "R8") (pin "2") (pinfunction "2_2") (pintype "passive"))
      (node (ref "U1") (pin "8") (pinfunction "FB2_8") (pintype "output"))
    )
    (net (code "25") (name "Net-(U1-~{EN1})") (class "Default")
      (node (ref "R3") (pin "2") (pinfunction "2_2") (pintype "passive"))
      (node (ref "TP6") (pin "1") (pinfunction "1_1") (pintype "passive"))
      (node (ref "U1") (pin "5") (pinfunction "~{EN1}_5") (pintype "input"))
    )
    (net (code "26") (name "unconnected-(J1-Pad01)") (class "Default")
      (node (ref "J1") (pin "01") (pinfunction "01_01") (pintype "passive+no_connect"))
    )
    (net (code "27") (name "unconnected-(J2-Pad01)") (class "Default")
      (node (ref "J2") (pin "01") (pinfunction "01_01") (pintype "passive+no_connect"))
    )
    (net (code "28") (name "unconnected-(J3-Pad01)") (class "Default")
      (node (ref "J3") (pin "01") (pinfunction "01_01") (pintype "passive+no_connect"))
    )
  )
)
